# KinetisCANBoard.net
KiCad netlist of a schematic drawn in Altium Designer
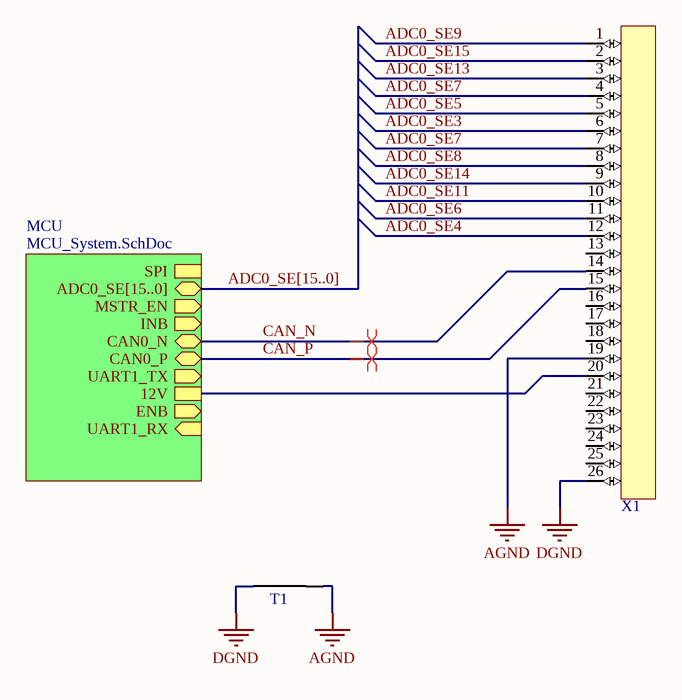
[diagram p0: KinetisCANBoard.SchDoc]

(export (version "E")
  (design (tool "Eeschema 10.0.6"))
  (components
    (comp (ref "T1")
      (value "Net Tie")
      (footprint "Net Tie 10mil")
      (libsource (lib "CPRacingUnifiedLibrary") (part "Net Tie"))
    )
    (comp (ref "X1")
      (value "TE Superseal 26 POS")
      (footprint "TE_SUPERSEAL_26")
      (libsource (lib "Components") (part "TE Superseal 26 POS"))
    )
  )
  (nets
    (net (code "6") (name "/12V") (class "Default") (node (ref "X1") (pin "20") (pintype "bidirectional")))
    (net (code "7") (name "/ADC0_SE3") (class "Default")
      (node (ref "X1") (pin "6") (pintype "bidirectional"))
    )
    (net (code "8") (name "/ADC0_SE4") (class "Default")
      (node (ref "X1") (pin "12") (pintype "bidirectional"))
    )
    (net (code "9") (name "/ADC0_SE5") (class "Default")
      (node (ref "X1") (pin "5") (pintype "bidirectional"))
    )
    (net (code "10") (name "/ADC0_SE6") (class "Default")
      (node (ref "X1") (pin "11") (pintype "bidirectional"))
    )
    (net (code "11") (name "/ADC0_SE7") (class "Default")
      (node (ref "X1") (pin "4") (pintype "bidirectional"))
      (node (ref "X1") (pin "7") (pintype "bidirectional"))
    )
    (net (code "12") (name "/ADC0_SE8") (class "Default")
      (node (ref "X1") (pin "8") (pintype "bidirectional"))
    )
    (net (code "13") (name "/ADC0_SE9") (class "Default")
      (node (ref "X1") (pin "1") (pintype "bidirectional"))
    )
    (net (code "14") (name "/ADC0_SE11") (class "Default")
      (node (ref "X1") (pin "10") (pintype "bidirectional"))
    )
    (net (code "15") (name "/ADC0_SE13") (class "Default")
      (node (ref "X1") (pin "3") (pintype "bidirectional"))
    )
    (net (code "16") (name "/ADC0_SE14") (class "Default")
      (node (ref "X1") (pin "9") (pintype "bidirectional"))
    )
    (net (code "17") (name "/ADC0_SE15") (class "Default")
      (node (ref "X1") (pin "2") (pintype "bidirectional"))
    )
    (net (code "19") (name "/CAN_N") (class "Default") (node (ref "X1") (pin "14") (pintype "bidirectional")))
    (net (code "20") (name "/CAN_P") (class "Default") (node (ref "X1") (pin "15") (pintype "bidirectional")))
    (net (code "27") (name "AGND") (class "Default")
      (node (ref "T1") (pin "2") (pinfunction "2_2") (pintype "passive"))
      (node (ref "X1") (pin "19") (pintype "bidirectional"))
    )
    (net (code "28") (name "DGND") (class "Default")
      (node (ref "T1") (pin "2") (pinfunction "11_2") (pintype "passive"))
      (node (ref "X1") (pin "26") (pintype "bidirectional"))
    )
    (net (code "29") (name "unconnected-(X1-Pad13)") (class "Default")
      (node (ref "X1") (pin "13") (pintype "bidirectional"))
    )
    (net (code "30") (name "unconnected-(X1-Pad16)") (class "Default")
      (node (ref "X1") (pin "16") (pintype "bidirectional"))
    )
    (net (code "31") (name "unconnected-(X1-Pad17)") (class "Default")
      (node (ref "X1") (pin "17") (pintype "bidirectional"))
    )
    (net (code "32") (name "unconnected-(X1-Pad18)") (class "Default")
      (node (ref "X1") (pin "18") (pintype "bidirectional"))
    )
    (net (code "33") (name "unconnected-(X1-Pad21)") (class "Default")
      (node (ref "X1") (pin "21") (pintype "bidirectional"))
    )
    (net (code "34") (name "unconnected-(X1-Pad22)") (class "Default")
      (node (ref "X1") (pin "22") (pintype "bidirectional"))
    )
    (net (code "35") (name "unconnected-(X1-Pad23)") (class "Default")
      (node (ref "X1") (pin "23") (pintype "bidirectional"))
    )
    (net (code "36") (name "unconnected-(X1-Pad24)") (class "Default")
      (node (ref "X1") (pin "24") (pintype "bidirectional"))
    )
    (net (code "37") (name "unconnected-(X1-Pad25)") (class "Default")
      (node (ref "X1") (pin "25") (pintype "bidirectional"))
    )
  )
)
